# Shematic.net
KiCad netlist of a schematic drawn in Altium Designer
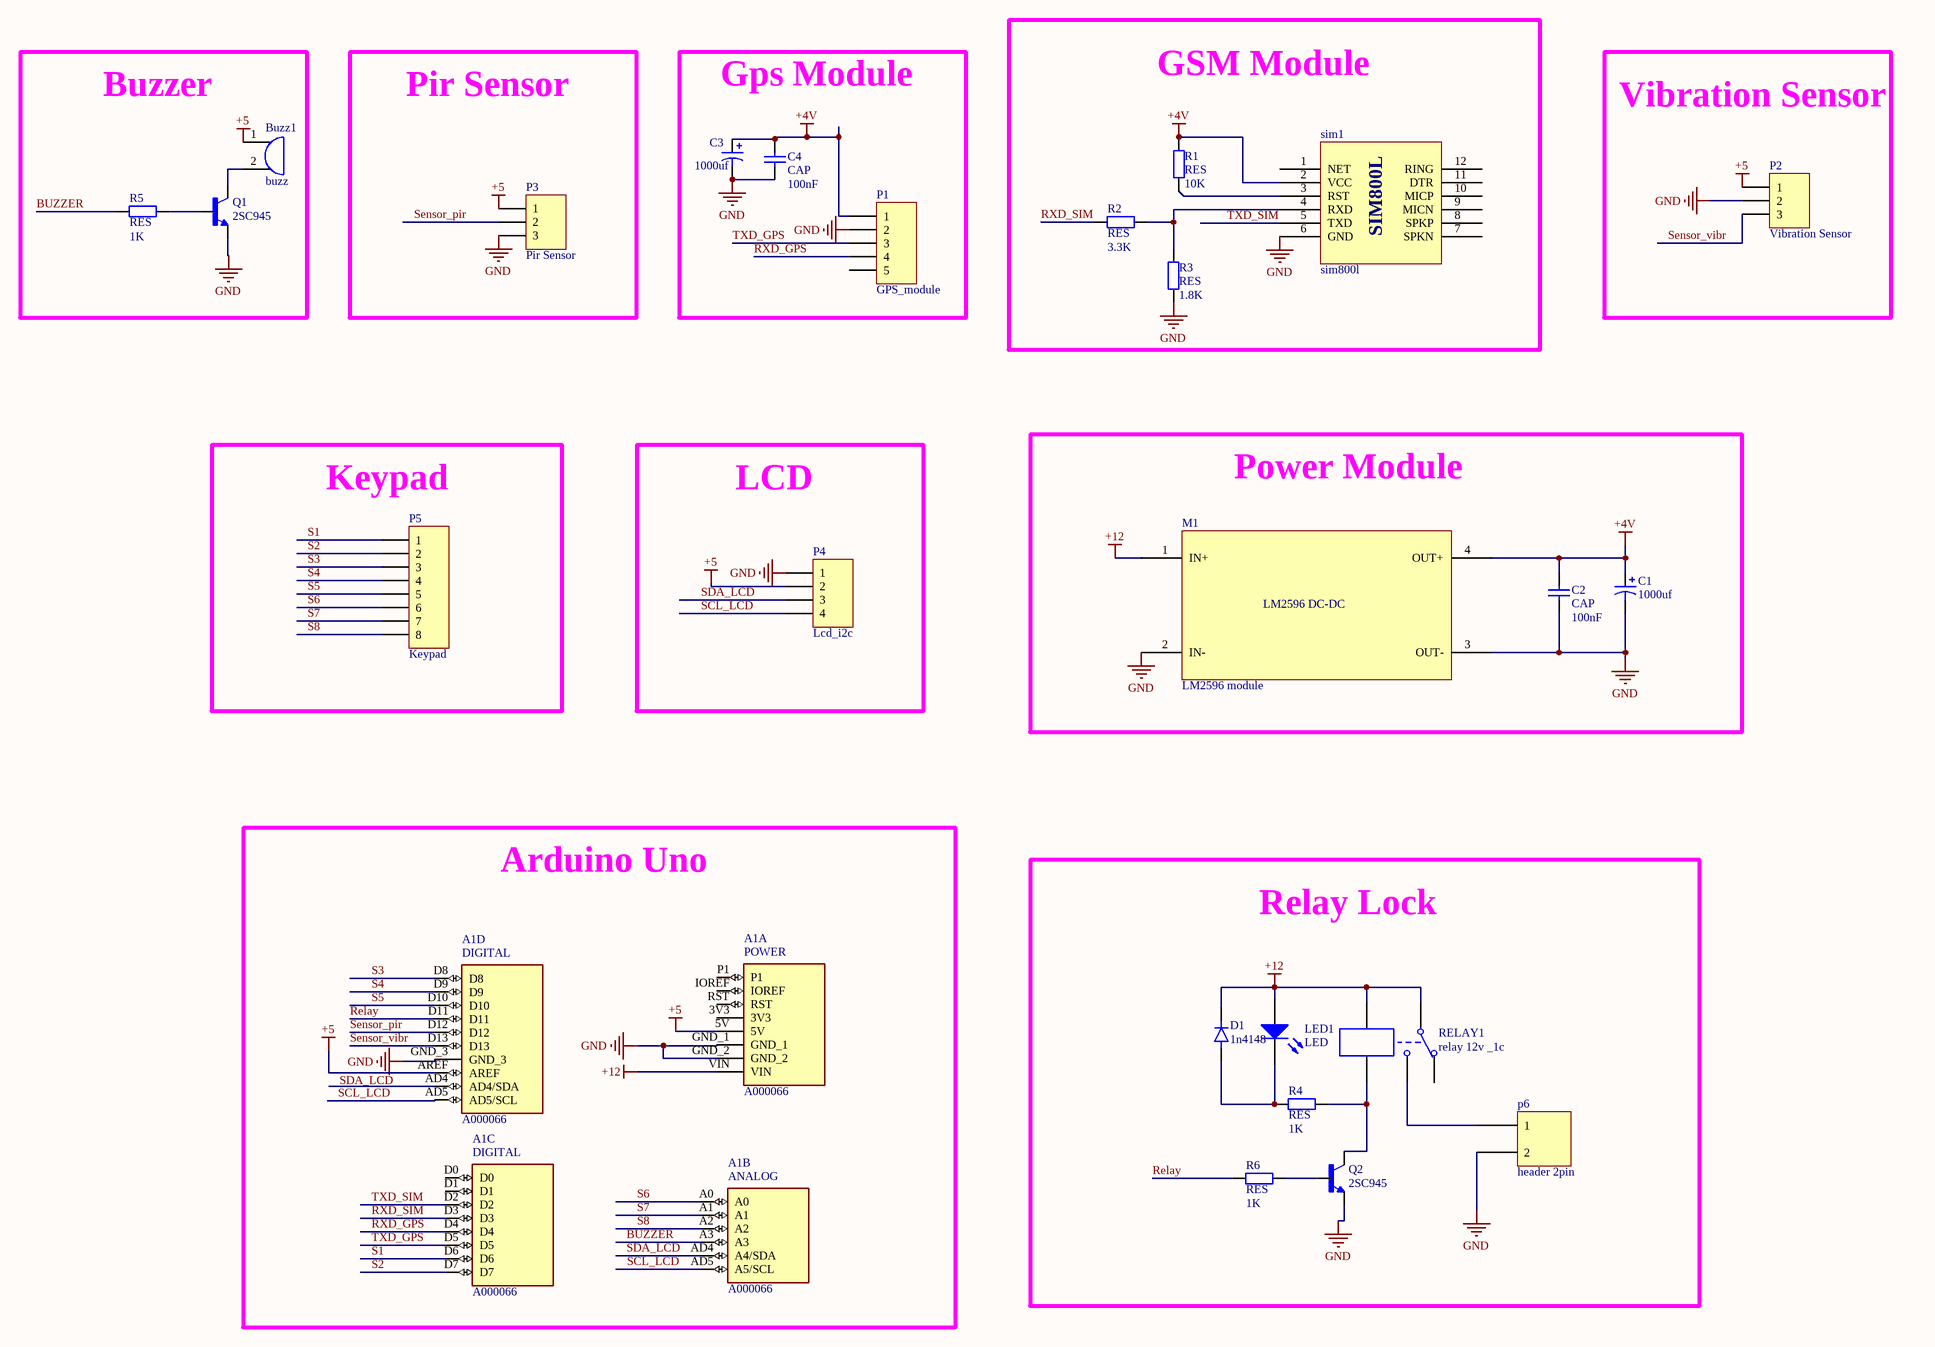
[diagram p0: Shematic.SchDoc]

(export (version "E")
  (design (tool "Eeschema 10.0.6"))
  (components
    (comp (ref "A1")
      (value "A000066")
      (footprint "ARDUINO_A000066")
      (description "Microcontroller board based on the ATmega328P.")
      (fields (field (name "MF") "Arduino") (field (name "MP") "Arduino Uno Rev3"))
      (libsource (lib "A000066") (part "A000066"))
    )
    (comp (ref "Buzz1") (value "buzz") (footprint "BUZZ") (libsource (lib "Reza_Lib") (part "buzz")))
    (comp (ref "C1") (value "1000uf") (footprint "CAP_POL5MM") (libsource (lib "Reza_Lib") (part "CAP_POL")))
    (comp (ref "C2")
      (value "CAP")
      (footprint "CAP2.54")
      (fields (field (name "PARAMETER 1") "100nF"))
      (libsource (lib "Reza_Lib") (part "CAP"))
    )
    (comp (ref "C3") (value "1000uf") (footprint "CAP_POL5MM") (libsource (lib "Reza_Lib") (part "CAP_POL")))
    (comp (ref "C4")
      (value "CAP")
      (footprint "CAP2.54")
      (fields (field (name "PARAMETER 1") "100nF"))
      (libsource (lib "Reza_Lib") (part "CAP"))
    )
    (comp (ref "D1")
      (value "1n4148")
      (footprint "do-35")
      (description "Diode Standard 100V 200mA Surface Mount SOD-80")
      (fields (field (name "MP") "LL4148") (field (name "MF") "ON Semiconductor"))
      (libsource (lib "Reza_Lib") (part "1n4148"))
    )
    (comp (ref "LED1") (value "LED") (footprint "led_5mm") (libsource (lib "Reza_Lib") (part "LED")))
    (comp (ref "M1")
      (value "LM2596 module")
      (footprint "LM2596_modoule")
      (libsource (lib "Reza_Lib") (part "LM2596 module"))
    )
    (comp (ref "P1")
      (value "GPS_module")
      (footprint "HDR1X5")
      (description "Header, 5-Pin")
      (fields (field (name "PUBLISHER") "Altium Limited"))
      (libsource (lib "Miscellaneous Connectors") (part "Header 5"))
    )
    (comp (ref "P2")
      (value "Vibration Sensor")
      (footprint "HDR1X3")
      (description "Header, 3-Pin")
      (fields (field (name "PUBLISHER") "Altium Limited"))
      (libsource (lib "Miscellaneous Connectors") (part "Header 3"))
    )
    (comp (ref "P3")
      (value "Pir Sensor")
      (footprint "HDR1X3")
      (description "Header, 3-Pin")
      (fields (field (name "PUBLISHER") "Altium Limited"))
      (libsource (lib "Miscellaneous Connectors") (part "Header 3"))
    )
    (comp (ref "P4")
      (value "Lcd_i2c")
      (footprint "HDR1X4")
      (description "Header, 4-Pin")
      (fields (field (name "PUBLISHER") "Altium Limited"))
      (libsource (lib "Miscellaneous Connectors") (part "Header 4"))
    )
    (comp (ref "P5")
      (value "Keypad")
      (footprint "HDR1X8")
      (description "Header, 8-Pin")
      (fields (field (name "PUBLISHER") "Altium Limited"))
      (libsource (lib "Miscellaneous Connectors") (part "Header 8"))
    )
    (comp (ref "p6")
      (value "header 2pin")
      (footprint "header_2pin")
      (libsource (lib "Reza_Lib") (part "header 2pin"))
    )
    (comp (ref "Q1")
      (value "2SC945")
      (footprint "SOT95P237X112-3N")
      (description "Bipolar _BJT_ Transistor NPN 50V 150mA 150MHz 400mW Through Hole TO-92")
      (fields (field (name "MF") "Simtek"))
      (libsource (lib "Reza_Lib") (part "2SC945"))
    )
    (comp (ref "Q2")
      (value "2SC945")
      (footprint "SOT95P237X112-3N")
      (description "Bipolar _BJT_ Transistor NPN 50V 150mA 150MHz 400mW Through Hole TO-92")
      (fields (field (name "MF") "Simtek"))
      (libsource (lib "Reza_Lib") (part "2SC945"))
    )
    (comp (ref "R1")
      (value "RES")
      (footprint "C1206")
      (fields (field (name "ALTIUM_VALUE") "10K"))
      (libsource (lib "") (part "RES_2"))
    )
    (comp (ref "R2")
      (value "RES")
      (footprint "RES_1/4W")
      (fields (field (name "ALTIUM_VALUE") "3.3K"))
      (libsource (lib "") (part "RES_1"))
    )
    (comp (ref "R3")
      (value "RES")
      (footprint "RES_1/4W")
      (fields (field (name "ALTIUM_VALUE") "1.8K"))
      (libsource (lib "") (part "RES_3"))
    )
    (comp (ref "R4")
      (value "RES")
      (footprint "C1206")
      (fields (field (name "ALTIUM_VALUE") "1K"))
      (libsource (lib "Reza_Lib") (part "RES"))
    )
    (comp (ref "R5")
      (value "RES")
      (footprint "C1206")
      (fields (field (name "ALTIUM_VALUE") "1K"))
      (libsource (lib "Reza_Lib") (part "RES"))
    )
    (comp (ref "R6")
      (value "RES")
      (footprint "C1206")
      (fields (field (name "ALTIUM_VALUE") "1K"))
      (libsource (lib "Reza_Lib") (part "RES"))
    )
    (comp (ref "RELAY1")
      (value "relay 12v _1c")
      (footprint "relay 12v 1c")
      (libsource (lib "Reza_Lib") (part "relay 12v _1c"))
    )
    (comp (ref "sim1") (value "sim800l") (footprint "SIM800_L") (libsource (lib "Reza_Lib") (part "sim800l")))
  )
  (nets
    (net (code "1") (name "+4V") (class "Default")
      (node (ref "C1") (pin "1") (pinfunction "1_1") (pintype "passive"))
      (node (ref "C2") (pin "2") (pinfunction "2_2") (pintype "passive"))
      (node (ref "C3") (pin "1") (pinfunction "1_1") (pintype "passive"))
      (node (ref "C4") (pin "2") (pinfunction "2_2") (pintype "passive"))
      (node (ref "M1") (pin "4") (pinfunction "OUT+_4") (pintype "passive"))
      (node (ref "P1") (pin "1") (pinfunction "1_1") (pintype "passive"))
      (node (ref "R1") (pin "2") (pinfunction "2_2") (pintype "passive"))
      (node (ref "sim1") (pin "2") (pinfunction "VCC_2") (pintype "passive"))
    )
    (net (code "2") (name "+5") (class "Default")
      (node (ref "A1") (pin "5V") (pinfunction "5V_5V") (pintype "power_in"))
      (node (ref "A1") (pin "AREF") (pinfunction "AREF_AREF") (pintype "bidirectional"))
      (node (ref "Buzz1") (pin "1") (pinfunction "+_1") (pintype "passive"))
      (node (ref "P2") (pin "1") (pinfunction "1_1") (pintype "passive"))
      (node (ref "P3") (pin "1") (pinfunction "1_1") (pintype "passive"))
      (node (ref "P4") (pin "2") (pinfunction "2_2") (pintype "passive"))
    )
    (net (code "3") (name "+12") (class "Default")
      (node (ref "A1") (pin "VIN") (pinfunction "VIN_VIN") (pintype "power_in"))
      (node (ref "D1") (pin "2") (pinfunction "K_2") (pintype "passive"))
      (node (ref "LED1") (pin "1") (pinfunction "A_1") (pintype "passive"))
      (node (ref "M1") (pin "1") (pinfunction "IN+_1") (pintype "passive"))
      (node (ref "RELAY1") (pin "1") (pinfunction "1_1") (pintype "passive"))
      (node (ref "RELAY1") (pin "4") (pinfunction "4_4") (pintype "passive"))
    )
    (net (code "4") (name "/BUZZER") (class "Default")
      (node (ref "A1") (pin "A3") (pinfunction "A3_A3") (pintype "bidirectional"))
      (node (ref "R5") (pin "2") (pinfunction "2_2") (pintype "passive"))
    )
    (net (code "5") (name "/RXD_GPS") (class "Default")
      (node (ref "A1") (pin "D4") (pinfunction "D4_D4") (pintype "bidirectional"))
      (node (ref "P1") (pin "4") (pinfunction "4_4") (pintype "passive"))
    )
    (net (code "6") (name "/RXD_SIM") (class "Default")
      (node (ref "A1") (pin "D3") (pinfunction "D3_D3") (pintype "bidirectional"))
      (node (ref "R2") (pin "1") (pinfunction "1_1") (pintype "passive"))
    )
    (net (code "7") (name "/Relay") (class "Default")
      (node (ref "A1") (pin "D11") (pinfunction "D11_D11") (pintype "bidirectional"))
      (node (ref "R6") (pin "2") (pinfunction "2_2") (pintype "passive"))
    )
    (net (code "8") (name "/S1") (class "Default")
      (node (ref "A1") (pin "D6") (pinfunction "D6_D6") (pintype "bidirectional"))
      (node (ref "P5") (pin "1") (pinfunction "1_1") (pintype "passive"))
    )
    (net (code "9") (name "/S2") (class "Default")
      (node (ref "A1") (pin "D7") (pinfunction "D7_D7") (pintype "bidirectional"))
      (node (ref "P5") (pin "2") (pinfunction "2_2") (pintype "passive"))
    )
    (net (code "10") (name "/S3") (class "Default")
      (node (ref "A1") (pin "D8") (pinfunction "D8_D8") (pintype "bidirectional"))
      (node (ref "P5") (pin "3") (pinfunction "3_3") (pintype "passive"))
    )
    (net (code "11") (name "/S4") (class "Default")
      (node (ref "A1") (pin "D9") (pinfunction "D9_D9") (pintype "bidirectional"))
      (node (ref "P5") (pin "4") (pinfunction "4_4") (pintype "passive"))
    )
    (net (code "12") (name "/S5") (class "Default")
      (node (ref "A1") (pin "D10") (pinfunction "D10_D10") (pintype "bidirectional"))
      (node (ref "P5") (pin "5") (pinfunction "5_5") (pintype "passive"))
    )
    (net (code "13") (name "/S6") (class "Default")
      (node (ref "A1") (pin "A0") (pinfunction "A0_A0") (pintype "bidirectional"))
      (node (ref "P5") (pin "6") (pinfunction "6_6") (pintype "passive"))
    )
    (net (code "14") (name "/S7") (class "Default")
      (node (ref "A1") (pin "A1") (pinfunction "A1_A1") (pintype "bidirectional"))
      (node (ref "P5") (pin "7") (pinfunction "7_7") (pintype "passive"))
    )
    (net (code "15") (name "/S8") (class "Default")
      (node (ref "A1") (pin "A2") (pinfunction "A2_A2") (pintype "bidirectional"))
      (node (ref "P5") (pin "8") (pinfunction "8_8") (pintype "passive"))
    )
    (net (code "16") (name "/SCL_LCD") (class "Default")
      (node (ref "A1") (pin "AD5") (pinfunction "AD5/SCL_AD5") (pintype "bidirectional"))
      (node (ref "P4") (pin "4") (pinfunction "4_4") (pintype "passive"))
    )
    (net (code "17") (name "/SDA_LCD") (class "Default")
      (node (ref "A1") (pin "AD4") (pinfunction "A4/SDA_AD4") (pintype "bidirectional"))
      (node (ref "P4") (pin "3") (pinfunction "3_3") (pintype "passive"))
    )
    (net (code "18") (name "/Sensor_pir") (class "Default")
      (node (ref "A1") (pin "D12") (pinfunction "D12_D12") (pintype "bidirectional"))
      (node (ref "P3") (pin "2") (pinfunction "2_2") (pintype "passive"))
    )
    (net (code "19") (name "/Sensor_vibr") (class "Default")
      (node (ref "A1") (pin "D13") (pinfunction "D13_D13") (pintype "bidirectional"))
      (node (ref "P2") (pin "3") (pinfunction "3_3") (pintype "passive"))
    )
    (net (code "20") (name "/TXD_GPS") (class "Default")
      (node (ref "A1") (pin "D5") (pinfunction "D5_D5") (pintype "bidirectional"))
      (node (ref "P1") (pin "3") (pinfunction "3_3") (pintype "passive"))
    )
    (net (code "21") (name "/TXD_SIM") (class "Default")
      (node (ref "A1") (pin "D2") (pinfunction "D2_D2") (pintype "bidirectional"))
      (node (ref "sim1") (pin "5") (pinfunction "TXD_5") (pintype "passive"))
    )
    (net (code "22") (name "GND") (class "Default")
      (node (ref "A1") (pin "GND_1") (pinfunction "GND_1_GND_1") (pintype "power_in"))
      (node (ref "A1") (pin "GND_2") (pinfunction "GND_2_GND_2") (pintype "power_in"))
      (node (ref "A1") (pin "GND_3") (pinfunction "GND_3_GND_3") (pintype "power_in"))
      (node (ref "C1") (pin "2") (pinfunction "2_2") (pintype "passive"))
      (node (ref "C2") (pin "1") (pinfunction "1_1") (pintype "passive"))
      (node (ref "C3") (pin "2") (pinfunction "2_2") (pintype "passive"))
      (node (ref "C4") (pin "1") (pinfunction "1_1") (pintype "passive"))
      (node (ref "M1") (pin "2") (pinfunction "IN-_2") (pintype "passive"))
      (node (ref "M1") (pin "3") (pinfunction "OUT-_3") (pintype "passive"))
      (node (ref "P1") (pin "2") (pinfunction "2_2") (pintype "passive"))
      (node (ref "P2") (pin "2") (pinfunction "2_2") (pintype "passive"))
      (node (ref "P3") (pin "3") (pinfunction "3_3") (pintype "passive"))
      (node (ref "P4") (pin "1") (pinfunction "1_1") (pintype "passive"))
      (node (ref "Q1") (pin "2") (pinfunction "E_2") (pintype "passive"))
      (node (ref "Q2") (pin "2") (pinfunction "E_2") (pintype "passive"))
      (node (ref "R3") (pin "2") (pinfunction "2_2") (pintype "passive"))
      (node (ref "p6") (pin "2") (pinfunction "2_2") (pintype "passive"))
      (node (ref "sim1") (pin "6") (pinfunction "GND_6") (pintype "passive"))
    )
    (net (code "23") (name "Net-(Buzz1--)") (class "Default")
      (node (ref "Buzz1") (pin "2") (pinfunction "-_2") (pintype "passive"))
      (node (ref "Q1") (pin "3") (pinfunction "C_3") (pintype "passive"))
    )
    (net (code "24") (name "Net-(D1-A)") (class "Default")
      (node (ref "D1") (pin "1") (pinfunction "A_1") (pintype "passive"))
      (node (ref "LED1") (pin "2") (pinfunction "K_2") (pintype "passive"))
      (node (ref "R4") (pin "2") (pinfunction "2_2") (pintype "passive"))
    )
    (net (code "25") (name "Net-(Q1-B)") (class "Default")
      (node (ref "Q1") (pin "1") (pinfunction "B_1") (pintype "passive"))
      (node (ref "R5") (pin "1") (pinfunction "1_1") (pintype "passive"))
    )
    (net (code "26") (name "Net-(Q2-B)") (class "Default")
      (node (ref "Q2") (pin "1") (pinfunction "B_1") (pintype "passive"))
      (node (ref "R6") (pin "1") (pinfunction "1_1") (pintype "passive"))
    )
    (net (code "27") (name "Net-(Q2-C)") (class "Default")
      (node (ref "Q2") (pin "3") (pinfunction "C_3") (pintype "passive"))
      (node (ref "R4") (pin "1") (pinfunction "1_1") (pintype "passive"))
      (node (ref "RELAY1") (pin "5") (pinfunction "5_5") (pintype "passive"))
    )
    (net (code "28") (name "Net-(RELAY1-Pad3)") (class "Default")
      (node (ref "RELAY1") (pin "3") (pinfunction "3_3") (pintype "passive"))
      (node (ref "p6") (pin "1") (pinfunction "1_1") (pintype "passive"))
    )
    (net (code "29") (name "Net-(sim1-RST)") (class "Default")
      (node (ref "R1") (pin "1") (pinfunction "1_1") (pintype "passive"))
      (node (ref "sim1") (pin "3") (pinfunction "RST_3") (pintype "passive"))
    )
    (net (code "30") (name "Net-(sim1-RXD)") (class "Default")
      (node (ref "R2") (pin "2") (pinfunction "2_2") (pintype "passive"))
      (node (ref "R3") (pin "1") (pinfunction "1_1") (pintype "passive"))
      (node (ref "sim1") (pin "4") (pinfunction "RXD_4") (pintype "passive"))
    )
    (net (code "31") (name "unconnected-(A1-Pad3V3)") (class "Default")
      (node (ref "A1") (pin "3V3") (pinfunction "3V3_3V3") (pintype "power_in"))
    )
    (net (code "32") (name "unconnected-(A1-PadD0)") (class "Default")
      (node (ref "A1") (pin "D0") (pinfunction "D0_D0") (pintype "bidirectional"))
    )
    (net (code "33") (name "unconnected-(A1-PadD1)") (class "Default")
      (node (ref "A1") (pin "D1") (pinfunction "D1_D1") (pintype "bidirectional"))
    )
    (net (code "34") (name "unconnected-(A1-PadIOREF)") (class "Default")
      (node (ref "A1") (pin "IOREF") (pinfunction "IOREF_IOREF") (pintype "bidirectional"))
    )
    (net (code "35") (name "unconnected-(A1-PadP1)") (class "Default")
      (node (ref "A1") (pin "P1") (pinfunction "P1_P1") (pintype "bidirectional"))
    )
    (net (code "36") (name "unconnected-(A1-PadRST)") (class "Default")
      (node (ref "A1") (pin "RST") (pinfunction "RST_RST") (pintype "bidirectional"))
    )
    (net (code "37") (name "unconnected-(A1B-A5{slash}SCL-PadAD5)") (class "Default")
      (node (ref "A1") (pin "AD5") (pinfunction "A5/SCL_AD5") (pintype "bidirectional"))
    )
    (net (code "38") (name "unconnected-(A1D-AD4{slash}SDA-PadAD4)") (class "Default")
      (node (ref "A1") (pin "AD4") (pinfunction "AD4/SDA_AD4") (pintype "bidirectional"))
    )
    (net (code "39") (name "unconnected-(P1-Pad5)") (class "Default")
      (node (ref "P1") (pin "5") (pinfunction "5_5") (pintype "passive"))
    )
    (net (code "40") (name "unconnected-(RELAY1-Pad2)") (class "Default")
      (node (ref "RELAY1") (pin "2") (pinfunction "2_2") (pintype "passive"))
    )
    (net (code "41") (name "unconnected-(sim1-DTR-Pad11)") (class "Default")
      (node (ref "sim1") (pin "11") (pinfunction "DTR_11") (pintype "passive"))
    )
    (net (code "42") (name "unconnected-(sim1-MICN-Pad9)") (class "Default")
      (node (ref "sim1") (pin "9") (pinfunction "MICN_9") (pintype "passive"))
    )
    (net (code "43") (name "unconnected-(sim1-MICP-Pad10)") (class "Default")
      (node (ref "sim1") (pin "10") (pinfunction "MICP_10") (pintype "passive"))
    )
    (net (code "44") (name "unconnected-(sim1-NET-Pad1)") (class "Default")
      (node (ref "sim1") (pin "1") (pinfunction "NET_1") (pintype "passive"))
    )
    (net (code "45") (name "unconnected-(sim1-RING-Pad12)") (class "Default")
      (node (ref "sim1") (pin "12") (pinfunction "RING_12") (pintype "passive"))
    )
    (net (code "46") (name "unconnected-(sim1-SPKN-Pad7)") (class "Default")
      (node (ref "sim1") (pin "7") (pinfunction "SPKN_7") (pintype "passive"))
    )
    (net (code "47") (name "unconnected-(sim1-SPKP-Pad8)") (class "Default")
      (node (ref "sim1") (pin "8") (pinfunction "SPKP_8") (pintype "passive"))
    )
  )
)
